# SMD_Brushed_Motor_Driver_V3.net
KiCad netlist of a schematic drawn in Altium Designer
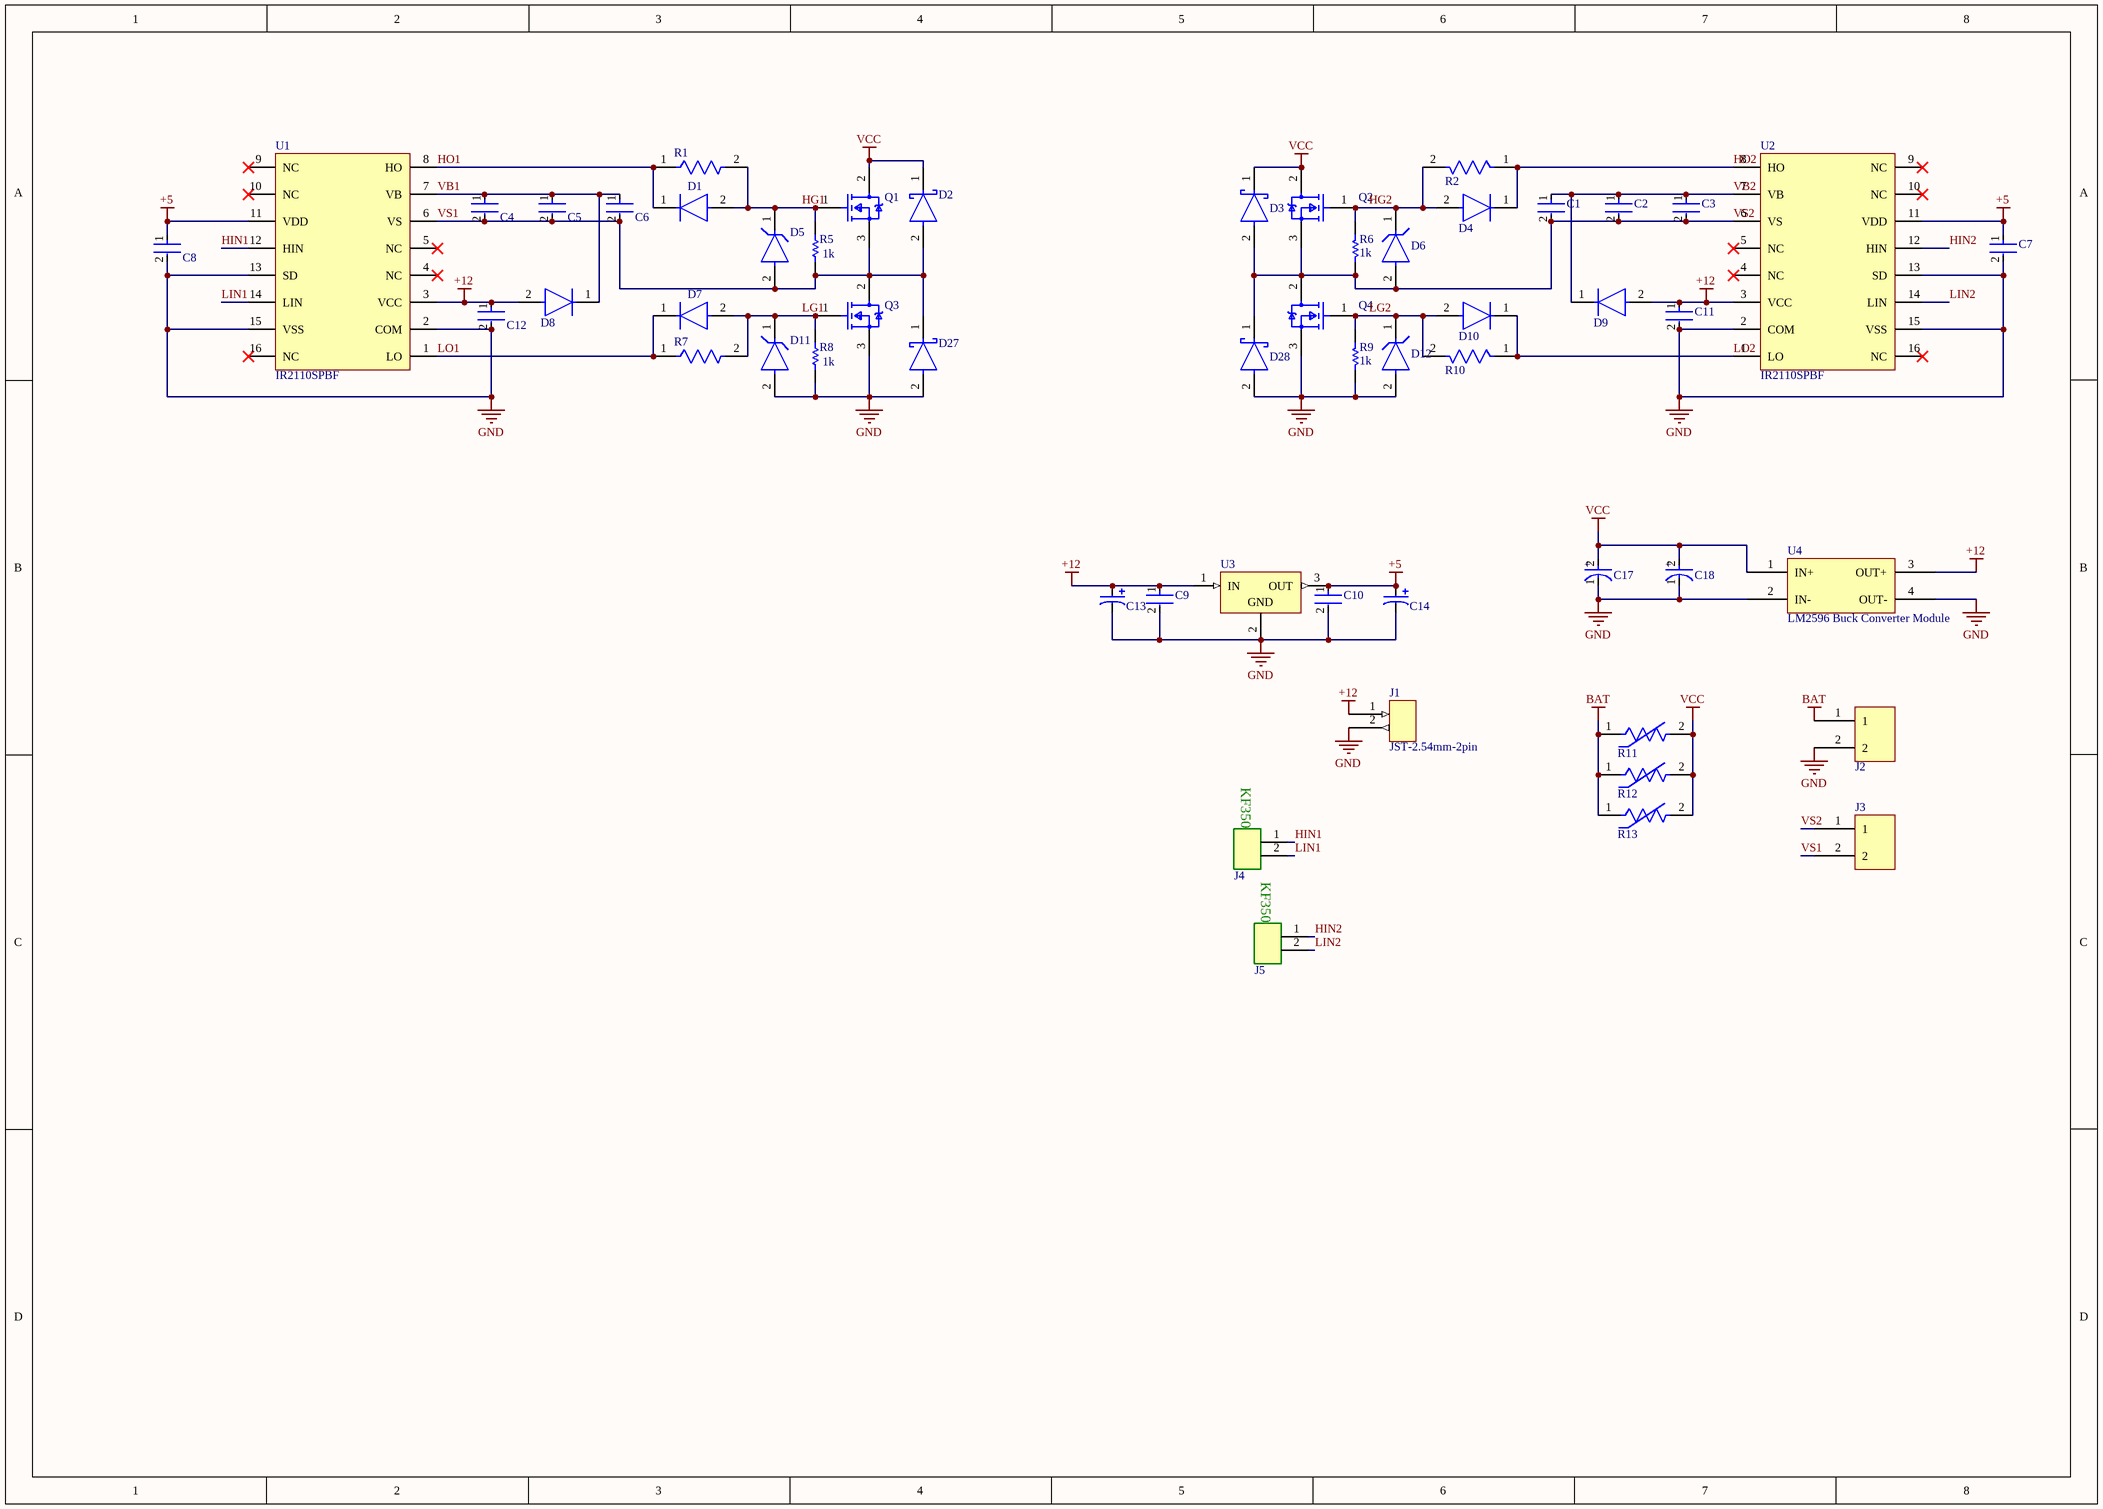
[diagram p0: SMD Brushed Motor Driver V3.SchDoc]

(export (version "E")
  (design (tool "Eeschema 10.0.6"))
  (components
    (comp (ref "C1")
      (value "12061C474KAT2A")
      (footprint "FP-1206-L_3_2_0_2-W_1_6_0-IPC_B")
      (description "1206 470 nF 100 V ±10 % Tolerance X7R Surface Mount Multilayer Ceramic Capacitor")
      (libsource (lib "ITU Autobee") (part "b4654b650e69147ec39a6b967a45e02"))
    )
    (comp (ref "C2")
      (value "12061C474KAT2A")
      (footprint "FP-1206-L_3_2_0_2-W_1_6_0-IPC_B")
      (description "1206 470 nF 100 V ±10 % Tolerance X7R Surface Mount Multilayer Ceramic Capacitor")
      (libsource (lib "ITU Autobee") (part "b4654b650e69147ec39a6b967a45e02"))
    )
    (comp (ref "C3")
      (value "12061C474KAT2A")
      (footprint "FP-1206-L_3_2_0_2-W_1_6_0-IPC_B")
      (description "1206 470 nF 100 V ±10 % Tolerance X7R Surface Mount Multilayer Ceramic Capacitor")
      (libsource (lib "ITU Autobee") (part "b4654b650e69147ec39a6b967a45e02"))
    )
    (comp (ref "C4")
      (value "12061C474KAT2A")
      (footprint "FP-1206-L_3_2_0_2-W_1_6_0-IPC_B")
      (description "1206 470 nF 100 V ±10 % Tolerance X7R Surface Mount Multilayer Ceramic Capacitor")
      (libsource (lib "ITU Autobee") (part "b4654b650e69147ec39a6b967a45e02"))
    )
    (comp (ref "C5")
      (value "12061C474KAT2A")
      (footprint "FP-1206-L_3_2_0_2-W_1_6_0-IPC_B")
      (description "1206 470 nF 100 V ±10 % Tolerance X7R Surface Mount Multilayer Ceramic Capacitor")
      (libsource (lib "ITU Autobee") (part "b4654b650e69147ec39a6b967a45e02"))
    )
    (comp (ref "C6")
      (value "12061C474KAT2A")
      (footprint "FP-1206-L_3_2_0_2-W_1_6_0-IPC_B")
      (description "1206 470 nF 100 V ±10 % Tolerance X7R Surface Mount Multilayer Ceramic Capacitor")
      (libsource (lib "ITU Autobee") (part "b4654b650e69147ec39a6b967a45e02"))
    )
    (comp (ref "C7")
      (value "12065C104KAT2A")
      (footprint "FP-1206-L_3_2_0_2-W_1_6_0-IPC_B")
      (description "Ceramic capacitor SMD-1206 100nF /50V X7R# K +-10%, AVX, RoHS, /4000 reel/")
      (libsource (lib "ITU Autobee") (part "02cd4be3c70576c341d710602a673aa"))
    )
    (comp (ref "C8")
      (value "12065C104KAT2A")
      (footprint "FP-1206-L_3_2_0_2-W_1_6_0-IPC_B")
      (description "Ceramic capacitor SMD-1206 100nF /50V X7R# K +-10%, AVX, RoHS, /4000 reel/")
      (libsource (lib "ITU Autobee") (part "02cd4be3c70576c341d710602a673aa"))
    )
    (comp (ref "C9")
      (value "12065C104KAT2A")
      (footprint "FP-1206-L_3_2_0_2-W_1_6_0-IPC_B")
      (description "Ceramic capacitor SMD-1206 100nF /50V X7R# K +-10%, AVX, RoHS, /4000 reel/")
      (libsource (lib "ITU Autobee") (part "02cd4be3c70576c341d710602a673aa"))
    )
    (comp (ref "C10")
      (value "12065C104KAT2A")
      (footprint "FP-1206-L_3_2_0_2-W_1_6_0-IPC_B")
      (description "Ceramic capacitor SMD-1206 100nF /50V X7R# K +-10%, AVX, RoHS, /4000 reel/")
      (libsource (lib "ITU Autobee") (part "02cd4be3c70576c341d710602a673aa"))
    )
    (comp (ref "C11")
      (value "12065C104KAT2A")
      (footprint "FP-1206-L_3_2_0_2-W_1_6_0-IPC_B")
      (description "Ceramic capacitor SMD-1206 100nF /50V X7R# K +-10%, AVX, RoHS, /4000 reel/")
      (libsource (lib "ITU Autobee") (part "02cd4be3c70576c341d710602a673aa"))
    )
    (comp (ref "C12")
      (value "12065C104KAT2A")
      (footprint "FP-1206-L_3_2_0_2-W_1_6_0-IPC_B")
      (description "Ceramic capacitor SMD-1206 100nF /50V X7R# K +-10%, AVX, RoHS, /4000 reel/")
      (libsource (lib "ITU Autobee") (part "02cd4be3c70576c341d710602a673aa"))
    )
    (comp (ref "C13")
      (value "22 uF TH Electrolytic Capacitor")
      (footprint "22 uF TH Electrolytic Capacitor-Footprint-1")
      (libsource (lib "ITU Autobee") (part "22 uF TH Electrolytic Capacitor-Symbol-1"))
    )
    (comp (ref "C14")
      (value "22 uF TH Electrolytic Capacitor")
      (footprint "22 uF TH Electrolytic Capacitor-Footprint-1")
      (libsource (lib "ITU Autobee") (part "22 uF TH Electrolytic Capacitor-Symbol-1"))
    )
    (comp (ref "C17")
      (value "ECA1VM222")
      (footprint "FP-RAD-TH-D_16_0_5-L_25_2-MFG")
      (description "Cap Aluminum 2200uF 35V 20% (16 X 25mm) Radial 7.5mm 1250mA 2000h 85°C Bulk")
      (libsource (lib "ITU Autobee") (part "203bc49f2ac43e59fd269a8c329ed05"))
    )
    (comp (ref "C18")
      (value "ECA1VM222")
      (footprint "FP-RAD-TH-D_16_0_5-L_25_2-MFG")
      (description "Cap Aluminum 2200uF 35V 20% (16 X 25mm) Radial 7.5mm 1250mA 2000h 85°C Bulk")
      (libsource (lib "ITU Autobee") (part "203bc49f2ac43e59fd269a8c329ed05"))
    )
    (comp (ref "D1")
      (value "MURS120T3G")
      (footprint "FP-403A-03-MFG")
      (description "VR=200V IF=2A Trr=35ns")
      (libsource (lib "ITU Autobee") (part "d7152d700b627762746794eb795d46e"))
    )
    (comp (ref "D2")
      (value "SS34-E3/57T")
      (footprint "FP-95402-MFG")
      (description "DIODE SCHOTTKY 40V 3A DO214AB")
      (libsource (lib "ITU Autobee") (part "1d6ec82d83fb6aee721767c19dac4b9"))
    )
    (comp (ref "D3")
      (value "SS34-E3/57T")
      (footprint "FP-95402-MFG")
      (description "DIODE SCHOTTKY 40V 3A DO214AB")
      (libsource (lib "ITU Autobee") (part "1d6ec82d83fb6aee721767c19dac4b9"))
    )
    (comp (ref "D4")
      (value "MURS120T3G")
      (footprint "FP-403A-03-MFG")
      (description "VR=200V IF=2A Trr=35ns")
      (libsource (lib "ITU Autobee") (part "d7152d700b627762746794eb795d46e"))
    )
    (comp (ref "D5")
      (value "TZMC3V3-GS08")
      (footprint "FP-6_560-5005_01-4-MFG")
      (description "DIODE ZENER 3.3V 500MW SOD80")
      (libsource (lib "ITU Autobee") (part "f813f71cba58e380607f5dd3caf9714"))
    )
    (comp (ref "D6")
      (value "TZMC3V3-GS08")
      (footprint "FP-6_560-5005_01-4-MFG")
      (description "DIODE ZENER 3.3V 500MW SOD80")
      (libsource (lib "ITU Autobee") (part "f813f71cba58e380607f5dd3caf9714"))
    )
    (comp (ref "D7")
      (value "MURS120T3G")
      (footprint "FP-403A-03-MFG")
      (description "VR=200V IF=2A Trr=35ns")
      (libsource (lib "ITU Autobee") (part "d7152d700b627762746794eb795d46e"))
    )
    (comp (ref "D8")
      (value "MURS120T3G")
      (footprint "FP-403A-03-MFG")
      (description "VR=200V IF=2A Trr=35ns")
      (libsource (lib "ITU Autobee") (part "d7152d700b627762746794eb795d46e"))
    )
    (comp (ref "D9")
      (value "MURS120T3G")
      (footprint "FP-403A-03-MFG")
      (description "VR=200V IF=2A Trr=35ns")
      (libsource (lib "ITU Autobee") (part "d7152d700b627762746794eb795d46e"))
    )
    (comp (ref "D10")
      (value "MURS120T3G")
      (footprint "FP-403A-03-MFG")
      (description "VR=200V IF=2A Trr=35ns")
      (libsource (lib "ITU Autobee") (part "d7152d700b627762746794eb795d46e"))
    )
    (comp (ref "D11")
      (value "TZMC3V3-GS08")
      (footprint "FP-6_560-5005_01-4-MFG")
      (description "DIODE ZENER 3.3V 500MW SOD80")
      (libsource (lib "ITU Autobee") (part "f813f71cba58e380607f5dd3caf9714"))
    )
    (comp (ref "D12")
      (value "TZMC3V3-GS08")
      (footprint "FP-6_560-5005_01-4-MFG")
      (description "DIODE ZENER 3.3V 500MW SOD80")
      (libsource (lib "ITU Autobee") (part "f813f71cba58e380607f5dd3caf9714"))
    )
    (comp (ref "D27")
      (value "SS34-E3/57T")
      (footprint "FP-95402-MFG")
      (description "DIODE SCHOTTKY 40V 3A DO214AB")
      (libsource (lib "ITU Autobee") (part "1d6ec82d83fb6aee721767c19dac4b9"))
    )
    (comp (ref "D28")
      (value "SS34-E3/57T")
      (footprint "FP-95402-MFG")
      (description "DIODE SCHOTTKY 40V 3A DO214AB")
      (libsource (lib "ITU Autobee") (part "1d6ec82d83fb6aee721767c19dac4b9"))
    )
    (comp (ref "J1")
      (value "JST-2.54mm-2pin")
      (footprint "New footprint 1")
      (description "2 pin konnektör")
      (libsource (lib "ITU Autobee") (part "Tunic Connector 2.54-2"))
    )
    (comp (ref "J2")
      (value "2 pin terminal klemens")
      (footprint "New footprint 1")
      (description "2 pin terminal klemens pin aralığı 200 mil")
      (libsource (lib "ITU Autobee") (part "2 pin terminal klemens schematic"))
    )
    (comp (ref "J3")
      (value "2 pin terminal klemens")
      (footprint "New footprint 1")
      (description "2 pin terminal klemens pin aralığı 200 mil")
      (libsource (lib "ITU Autobee") (part "2 pin terminal klemens schematic"))
    )
    (comp (ref "J4")
      (value "KF350-P2")
      (footprint "New footprint 1")
      (description "3.5mm mini klemens")
      (libsource (lib "ITU Autobee") (part "New symbol 1"))
    )
    (comp (ref "J5")
      (value "KF350-P2")
      (footprint "New footprint 1")
      (description "3.5mm mini klemens")
      (libsource (lib "ITU Autobee") (part "New symbol 1"))
    )
    (comp (ref "Q1")
      (value "IRF3205STRLPBF")
      (footprint "FP-PG-TO263-3-MFG")
      (description "MOSFET N-CH 55V 110A D2PAK")
      (libsource (lib "ITU Autobee") (part "b09f7f152735e370c1ea22a33fa83d6"))
    )
    (comp (ref "Q2")
      (value "IRF3205STRLPBF")
      (footprint "FP-PG-TO263-3-MFG")
      (description "MOSFET N-CH 55V 110A D2PAK")
      (libsource (lib "ITU Autobee") (part "b09f7f152735e370c1ea22a33fa83d6"))
    )
    (comp (ref "Q3")
      (value "IRF3205STRLPBF")
      (footprint "FP-PG-TO263-3-MFG")
      (description "MOSFET N-CH 55V 110A D2PAK")
      (libsource (lib "ITU Autobee") (part "b09f7f152735e370c1ea22a33fa83d6"))
    )
    (comp (ref "Q4")
      (value "IRF3205STRLPBF")
      (footprint "FP-PG-TO263-3-MFG")
      (description "MOSFET N-CH 55V 110A D2PAK")
      (libsource (lib "ITU Autobee") (part "b09f7f152735e370c1ea22a33fa83d6"))
    )
    (comp (ref "R1")
      (value "RC1206JR-0710RL")
      (footprint "FP-RC1206-0_65-MFG")
      (description "Res General Purpose Thick Film 1206 10 Ohm 5% 1/4W ±200ppm/°C Molded SMD Paper T/R")
      (libsource (lib "ITU Autobee") (part "8db39607336c341a927600551d01821"))
    )
    (comp (ref "R2")
      (value "RC1206JR-0710RL")
      (footprint "FP-RC1206-0_65-MFG")
      (description "Res General Purpose Thick Film 1206 10 Ohm 5% 1/4W ±200ppm/°C Molded SMD Paper T/R")
      (libsource (lib "ITU Autobee") (part "8db39607336c341a927600551d01821"))
    )
    (comp (ref "R5")
      (value "1k")
      (footprint "RESC3116X70X50ML13T20")
      (description "Chip Resistor, 1 KOhm, +/- 1%, 0.25 W, -55 to 155 degC, 1206 (3216 Metric)")
      (fields (field (name "TOLERANCE") "1%") (field (name "POWER") "250mW"))
      (libsource (lib "ITU Autobee") (part "RES-2"))
    )
    (comp (ref "R6")
      (value "1k")
      (footprint "RESC3116X70X50ML13T20")
      (description "Chip Resistor, 1 KOhm, +/- 1%, 0.25 W, -55 to 155 degC, 1206 (3216 Metric)")
      (fields (field (name "TOLERANCE") "1%") (field (name "POWER") "250mW"))
      (libsource (lib "ITU Autobee") (part "RES-2"))
    )
    (comp (ref "R7")
      (value "RC1206JR-0710RL")
      (footprint "FP-RC1206-0_65-MFG")
      (description "Res General Purpose Thick Film 1206 10 Ohm 5% 1/4W ±200ppm/°C Molded SMD Paper T/R")
      (libsource (lib "ITU Autobee") (part "8db39607336c341a927600551d01821"))
    )
    (comp (ref "R8")
      (value "1k")
      (footprint "RESC3116X70X50ML13T20")
      (description "Chip Resistor, 1 KOhm, +/- 1%, 0.25 W, -55 to 155 degC, 1206 (3216 Metric)")
      (fields (field (name "TOLERANCE") "1%") (field (name "POWER") "250mW"))
      (libsource (lib "ITU Autobee") (part "RES-2"))
    )
    (comp (ref "R9")
      (value "1k")
      (footprint "RESC3116X70X50ML13T20")
      (description "Chip Resistor, 1 KOhm, +/- 1%, 0.25 W, -55 to 155 degC, 1206 (3216 Metric)")
      (fields (field (name "TOLERANCE") "1%") (field (name "POWER") "250mW"))
      (libsource (lib "ITU Autobee") (part "RES-2"))
    )
    (comp (ref "R10")
      (value "RC1206JR-0710RL")
      (footprint "FP-RC1206-0_65-MFG")
      (description "Res General Purpose Thick Film 1206 10 Ohm 5% 1/4W ±200ppm/°C Molded SMD Paper T/R")
      (libsource (lib "ITU Autobee") (part "8db39607336c341a927600551d01821"))
    )
    (comp (ref "R11")
      (value "20mm Body 7.5mm pitch Thermistor")
      (footprint "FP-NTPAD-MFG")
      (libsource (lib "ITU Autobee") (part "3b148a6ebabc5fb4d708a66c052d352"))
    )
    (comp (ref "R12")
      (value "20mm Body 7.5mm pitch Thermistor")
      (footprint "FP-NTPAD-MFG")
      (libsource (lib "ITU Autobee") (part "3b148a6ebabc5fb4d708a66c052d352"))
    )
    (comp (ref "R13")
      (value "20mm Body 7.5mm pitch Thermistor")
      (footprint "FP-NTPAD-MFG")
      (libsource (lib "ITU Autobee") (part "3b148a6ebabc5fb4d708a66c052d352"))
    )
    (comp (ref "U1")
      (value "IR2110SPBF")
      (footprint "IR2110SPBF-Footprint-1")
      (description "500 V high-side and low-side gate driver IC with shutdown, SOIC 16W, RoHS")
      (libsource (lib "ITU Autobee") (part "IR2110SPBF-Symbol-1"))
    )
    (comp (ref "U2")
      (value "IR2110SPBF")
      (footprint "IR2110SPBF-Footprint-1")
      (description "500 V high-side and low-side gate driver IC with shutdown, SOIC 16W, RoHS")
      (libsource (lib "") (part "IR2110SPBF-Symbol-1_1"))
    )
    (comp (ref "U3")
      (value "LM7805CT")
      (footprint "FAIR-TO-220-3")
      (description "LM78XX Series 5 V Fixed Output 1 A 3-Terminal LDO Voltage Regulator - TO-220")
      (libsource (lib "ITU Autobee") (part "FAIR-LM7805CT-TO220-3"))
    )
    (comp (ref "U4")
      (value "LM2596 Buck Converter Module")
      (footprint "LM2596 Buck Converter Module-Footprint-1")
      (libsource (lib "ITU Autobee") (part "LM2596 Buck Converter Module Symbol"))
    )
  )
  (nets
    (net (code "1") (name "+5") (class "Default")
      (node (ref "C10") (pin "1") (pinfunction "1_1") (pintype "passive"))
      (node (ref "C14") (pin "1") (pinfunction "1_1") (pintype "passive"))
      (node (ref "C7") (pin "1") (pinfunction "1_1") (pintype "passive"))
      (node (ref "C8") (pin "1") (pinfunction "1_1") (pintype "passive"))
      (node (ref "U1") (pin "11") (pinfunction "VDD_11") (pintype "passive"))
      (node (ref "U2") (pin "11") (pinfunction "VDD_11") (pintype "passive"))
      (node (ref "U3") (pin "3") (pinfunction "OUT_3") (pintype "output"))
    )
    (net (code "2") (name "+12") (class "Default")
      (node (ref "C11") (pin "1") (pinfunction "1_1") (pintype "passive"))
      (node (ref "C12") (pin "1") (pinfunction "1_1") (pintype "passive"))
      (node (ref "C13") (pin "1") (pinfunction "1_1") (pintype "passive"))
      (node (ref "C9") (pin "1") (pinfunction "1_1") (pintype "passive"))
      (node (ref "D8") (pin "2") (pinfunction "A_2") (pintype "passive"))
      (node (ref "D9") (pin "2") (pinfunction "A_2") (pintype "passive"))
      (node (ref "J1") (pin "1") (pintype "input"))
      (node (ref "U1") (pin "3") (pinfunction "VCC_3") (pintype "passive"))
      (node (ref "U2") (pin "3") (pinfunction "VCC_3") (pintype "passive"))
      (node (ref "U3") (pin "1") (pinfunction "IN_1") (pintype "input"))
      (node (ref "U4") (pin "3") (pinfunction "OUT+_3") (pintype "passive"))
    )
    (net (code "3") (name "/HG1") (class "Default")
      (node (ref "D1") (pin "2") (pinfunction "A_2") (pintype "passive"))
      (node (ref "D5") (pin "1") (pinfunction "C_1") (pintype "passive"))
      (node (ref "Q1") (pin "1") (pinfunction "G_1") (pintype "passive"))
      (node (ref "R1") (pin "2") (pinfunction "2_2") (pintype "passive"))
      (node (ref "R5") (pin "1") (pinfunction "1_1") (pintype "passive"))
    )
    (net (code "4") (name "/HG2") (class "Default")
      (node (ref "D4") (pin "2") (pinfunction "A_2") (pintype "passive"))
      (node (ref "D6") (pin "1") (pinfunction "C_1") (pintype "passive"))
      (node (ref "Q2") (pin "1") (pinfunction "G_1") (pintype "passive"))
      (node (ref "R2") (pin "2") (pinfunction "2_2") (pintype "passive"))
      (node (ref "R6") (pin "1") (pinfunction "1_1") (pintype "passive"))
    )
    (net (code "5") (name "/HIN1") (class "Default")
      (node (ref "J4") (pin "1") (pinfunction "1_1") (pintype "passive"))
      (node (ref "U1") (pin "12") (pinfunction "HIN_12") (pintype "passive"))
    )
    (net (code "6") (name "/HIN2") (class "Default")
      (node (ref "J5") (pin "1") (pinfunction "1_1") (pintype "passive"))
      (node (ref "U2") (pin "12") (pinfunction "HIN_12") (pintype "passive"))
    )
    (net (code "7") (name "/HO1") (class "Default")
      (node (ref "D1") (pin "1") (pinfunction "C_1") (pintype "passive"))
      (node (ref "R1") (pin "1") (pinfunction "1_1") (pintype "passive"))
      (node (ref "U1") (pin "8") (pinfunction "HO_8") (pintype "passive"))
    )
    (net (code "8") (name "/HO2") (class "Default")
      (node (ref "D4") (pin "1") (pinfunction "C_1") (pintype "passive"))
      (node (ref "R2") (pin "1") (pinfunction "1_1") (pintype "passive"))
      (node (ref "U2") (pin "8") (pinfunction "HO_8") (pintype "passive"))
    )
    (net (code "9") (name "/LG1") (class "Default")
      (node (ref "D11") (pin "1") (pinfunction "C_1") (pintype "passive"))
      (node (ref "D7") (pin "2") (pinfunction "A_2") (pintype "passive"))
      (node (ref "Q3") (pin "1") (pinfunction "G_1") (pintype "passive"))
      (node (ref "R7") (pin "2") (pinfunction "2_2") (pintype "passive"))
      (node (ref "R8") (pin "1") (pinfunction "1_1") (pintype "passive"))
    )
    (net (code "10") (name "/LG2") (class "Default")
      (node (ref "D10") (pin "2") (pinfunction "A_2") (pintype "passive"))
      (node (ref "D12") (pin "1") (pinfunction "C_1") (pintype "passive"))
      (node (ref "Q4") (pin "1") (pinfunction "G_1") (pintype "passive"))
      (node (ref "R10") (pin "2") (pinfunction "2_2") (pintype "passive"))
      (node (ref "R9") (pin "1") (pinfunction "1_1") (pintype "passive"))
    )
    (net (code "11") (name "/LIN1") (class "Default")
      (node (ref "J4") (pin "2") (pinfunction "2_2") (pintype "passive"))
      (node (ref "U1") (pin "14") (pinfunction "LIN_14") (pintype "passive"))
    )
    (net (code "12") (name "/LIN2") (class "Default")
      (node (ref "J5") (pin "2") (pinfunction "2_2") (pintype "passive"))
      (node (ref "U2") (pin "14") (pinfunction "LIN_14") (pintype "passive"))
    )
    (net (code "13") (name "/LO1") (class "Default")
      (node (ref "D7") (pin "1") (pinfunction "C_1") (pintype "passive"))
      (node (ref "R7") (pin "1") (pinfunction "1_1") (pintype "passive"))
      (node (ref "U1") (pin "1") (pinfunction "LO_1") (pintype "passive"))
    )
    (net (code "14") (name "/LO2") (class "Default")
      (node (ref "D10") (pin "1") (pinfunction "C_1") (pintype "passive"))
      (node (ref "R10") (pin "1") (pinfunction "1_1") (pintype "passive"))
      (node (ref "U2") (pin "1") (pinfunction "LO_1") (pintype "passive"))
    )
    (net (code "15") (name "/VB1") (class "Default")
      (node (ref "C4") (pin "1") (pinfunction "1_1") (pintype "passive"))
      (node (ref "C5") (pin "1") (pinfunction "1_1") (pintype "passive"))
      (node (ref "C6") (pin "1") (pinfunction "1_1") (pintype "passive"))
      (node (ref "D8") (pin "1") (pinfunction "C_1") (pintype "passive"))
      (node (ref "U1") (pin "7") (pinfunction "VB_7") (pintype "passive"))
    )
    (net (code "16") (name "/VB2") (class "Default")
      (node (ref "C1") (pin "1") (pinfunction "1_1") (pintype "passive"))
      (node (ref "C2") (pin "1") (pinfunction "1_1") (pintype "passive"))
      (node (ref "C3") (pin "1") (pinfunction "1_1") (pintype "passive"))
      (node (ref "D9") (pin "1") (pinfunction "C_1") (pintype "passive"))
      (node (ref "U2") (pin "7") (pinfunction "VB_7") (pintype "passive"))
    )
    (net (code "17") (name "/VS1") (class "Default")
      (node (ref "C4") (pin "2") (pinfunction "2_2") (pintype "passive"))
      (node (ref "C5") (pin "2") (pinfunction "2_2") (pintype "passive"))
      (node (ref "C6") (pin "2") (pinfunction "2_2") (pintype "passive"))
      (node (ref "D2") (pin "2") (pinfunction "A_2") (pintype "passive"))
      (node (ref "D27") (pin "1") (pinfunction "C_1") (pintype "passive"))
      (node (ref "D5") (pin "2") (pinfunction "A_2") (pintype "passive"))
      (node (ref "J3") (pin "2") (pinfunction "2_2") (pintype "passive"))
      (node (ref "Q1") (pin "3") (pinfunction "S_3") (pintype "passive"))
      (node (ref "Q3") (pin "2") (pinfunction "D_2") (pintype "passive"))
      (node (ref "R5") (pin "2") (pinfunction "2_2") (pintype "passive"))
      (node (ref "U1") (pin "6") (pinfunction "VS_6") (pintype "passive"))
    )
    (net (code "18") (name "/VS2") (class "Default")
      (node (ref "C1") (pin "2") (pinfunction "2_2") (pintype "passive"))
      (node (ref "C2") (pin "2") (pinfunction "2_2") (pintype "passive"))
      (node (ref "C3") (pin "2") (pinfunction "2_2") (pintype "passive"))
      (node (ref "D28") (pin "1") (pinfunction "C_1") (pintype "passive"))
      (node (ref "D3") (pin "2") (pinfunction "A_2") (pintype "passive"))
      (node (ref "D6") (pin "2") (pinfunction "A_2") (pintype "passive"))
      (node (ref "J3") (pin "1") (pinfunction "1_1") (pintype "passive"))
      (node (ref "Q2") (pin "3") (pinfunction "S_3") (pintype "passive"))
      (node (ref "Q4") (pin "2") (pinfunction "D_2") (pintype "passive"))
      (node (ref "R6") (pin "2") (pinfunction "2_2") (pintype "passive"))
      (node (ref "U2") (pin "6") (pinfunction "VS_6") (pintype "passive"))
    )
    (net (code "19") (name "BAT") (class "Default")
      (node (ref "J2") (pin "1") (pinfunction "1_1") (pintype "passive"))
      (node (ref "R11") (pin "1") (pinfunction "1_1") (pintype "passive"))
      (node (ref "R12") (pin "1") (pinfunction "1_1") (pintype "passive"))
      (node (ref "R13") (pin "1") (pinfunction "1_1") (pintype "passive"))
    )
    (net (code "20") (name "GND") (class "Default")
      (node (ref "C10") (pin "2") (pinfunction "2_2") (pintype "passive"))
      (node (ref "C11") (pin "2") (pinfunction "2_2") (pintype "passive"))
      (node (ref "C12") (pin "2") (pinfunction "2_2") (pintype "passive"))
      (node (ref "C13") (pin "2") (pinfunction "2_2") (pintype "passive"))
      (node (ref "C14") (pin "2") (pinfunction "2_2") (pintype "passive"))
      (node (ref "C17") (pin "1") (pinfunction "C_1") (pintype "passive"))
      (node (ref "C18") (pin "1") (pinfunction "C_1") (pintype "passive"))
      (node (ref "C7") (pin "2") (pinfunction "2_2") (pintype "passive"))
      (node (ref "C8") (pin "2") (pinfunction "2_2") (pintype "passive"))
      (node (ref "C9") (pin "2") (pinfunction "2_2") (pintype "passive"))
      (node (ref "D11") (pin "2") (pinfunction "A_2") (pintype "passive"))
      (node (ref "D12") (pin "2") (pinfunction "A_2") (pintype "passive"))
      (node (ref "D27") (pin "2") (pinfunction "A_2") (pintype "passive"))
      (node (ref "D28") (pin "2") (pinfunction "A_2") (pintype "passive"))
      (node (ref "J1") (pin "2") (pintype "output"))
      (node (ref "J2") (pin "2") (pinfunction "2_2") (pintype "passive"))
      (node (ref "Q3") (pin "3") (pinfunction "S_3") (pintype "passive"))
      (node (ref "Q4") (pin "3") (pinfunction "S_3") (pintype "passive"))
      (node (ref "R8") (pin "2") (pinfunction "2_2") (pintype "passive"))
      (node (ref "R9") (pin "2") (pinfunction "2_2") (pintype "passive"))
      (node (ref "U1") (pin "13") (pinfunction "SD_13") (pintype "passive"))
      (node (ref "U1") (pin "15") (pinfunction "VSS_15") (pintype "passive"))
      (node (ref "U1") (pin "2") (pinfunction "COM_2") (pintype "passive"))
      (node (ref "U2") (pin "13") (pinfunction "SD_13") (pintype "passive"))
      (node (ref "U2") (pin "15") (pinfunction "VSS_15") (pintype "passive"))
      (node (ref "U2") (pin "2") (pinfunction "COM_2") (pintype "passive"))
      (node (ref "U3") (pin "2") (pinfunction "GND_2") (pintype "power_in"))
      (node (ref "U4") (pin "2") (pinfunction "IN-_2") (pintype "passive"))
      (node (ref "U4") (pin "4") (pinfunction "OUT-_4") (pintype "passive"))
    )
    (net (code "21") (name "VCC") (class "Default")
      (node (ref "C17") (pin "2") (pinfunction "A_2") (pintype "passive"))
      (node (ref "C18") (pin "2") (pinfunction "A_2") (pintype "passive"))
      (node (ref "D2") (pin "1") (pinfunction "C_1") (pintype "passive"))
      (node (ref "D3") (pin "1") (pinfunction "C_1") (pintype "passive"))
      (node (ref "Q1") (pin "2") (pinfunction "D_2") (pintype "passive"))
      (node (ref "Q2") (pin "2") (pinfunction "D_2") (pintype "passive"))
      (node (ref "R11") (pin "2") (pinfunction "2_2") (pintype "passive"))
      (node (ref "R12") (pin "2") (pinfunction "2_2") (pintype "passive"))
      (node (ref "R13") (pin "2") (pinfunction "2_2") (pintype "passive"))
      (node (ref "U4") (pin "1") (pinfunction "IN+_1") (pintype "passive"))
    )
    (net (code "22") (name "unconnected-(U1-NC-Pad4)") (class "Default")
      (node (ref "U1") (pin "4") (pinfunction "NC_4") (pintype "passive+no_connect"))
    )
    (net (code "23") (name "unconnected-(U1-NC-Pad5)") (class "Default")
      (node (ref "U1") (pin "5") (pinfunction "NC_5") (pintype "passive+no_connect"))
    )
    (net (code "24") (name "unconnected-(U1-NC-Pad9)") (class "Default")
      (node (ref "U1") (pin "9") (pinfunction "NC_9") (pintype "passive+no_connect"))
    )
    (net (code "25") (name "unconnected-(U1-NC-Pad10)") (class "Default")
      (node (ref "U1") (pin "10") (pinfunction "NC_10") (pintype "passive+no_connect"))
    )
    (net (code "26") (name "unconnected-(U1-NC-Pad16)") (class "Default")
      (node (ref "U1") (pin "16") (pinfunction "NC_16") (pintype "passive+no_connect"))
    )
    (net (code "27") (name "unconnected-(U2-NC-Pad4)") (class "Default")
      (node (ref "U2") (pin "4") (pinfunction "NC_4") (pintype "passive+no_connect"))
    )
    (net (code "28") (name "unconnected-(U2-NC-Pad5)") (class "Default")
      (node (ref "U2") (pin "5") (pinfunction "NC_5") (pintype "passive+no_connect"))
    )
    (net (code "29") (name "unconnected-(U2-NC-Pad9)") (class "Default")
      (node (ref "U2") (pin "9") (pinfunction "NC_9") (pintype "passive+no_connect"))
    )
    (net (code "30") (name "unconnected-(U2-NC-Pad10)") (class "Default")
      (node (ref "U2") (pin "10") (pinfunction "NC_10") (pintype "passive+no_connect"))
    )
    (net (code "31") (name "unconnected-(U2-NC-Pad16)") (class "Default")
      (node (ref "U2") (pin "16") (pinfunction "NC_16") (pintype "passive+no_connect"))
    )
  )
)
